# preamp_gain_stage_2.net
KiCad netlist of a schematic drawn in Altium Designer
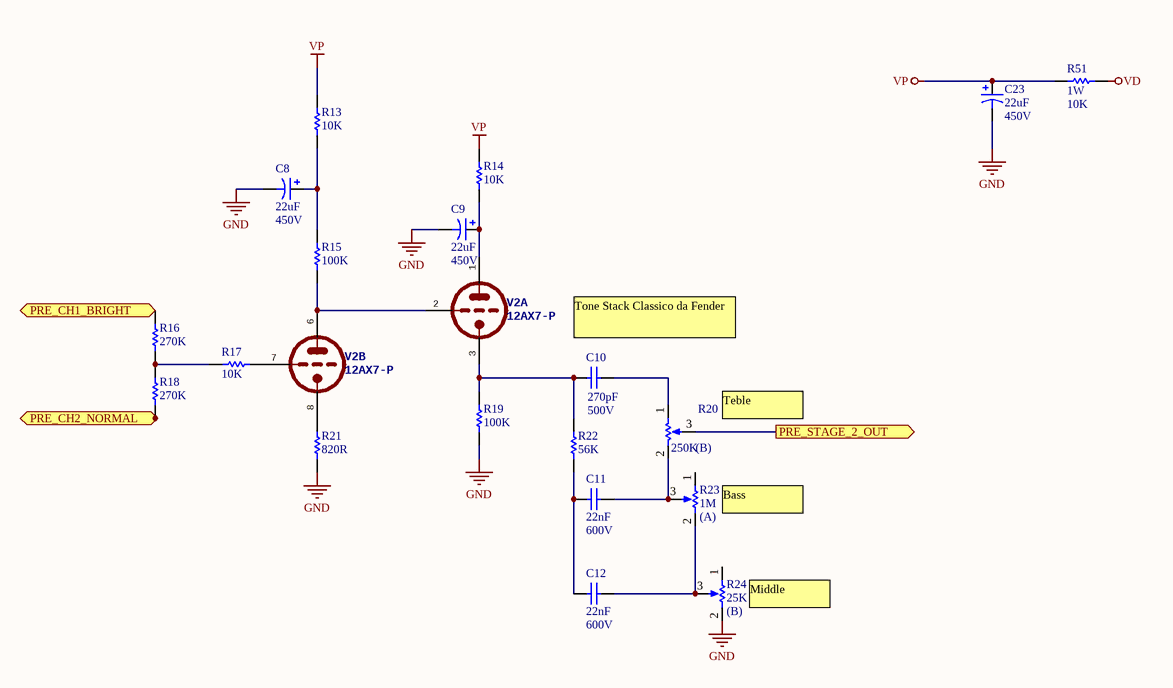
[diagram p0: preamp_gain_stage_2.SchDoc]

(export (version "E")
  (design (tool "Eeschema 10.0.6"))
  (components
    (comp (ref "C8")
      (value "22uF")
      (footprint "RAD-POL-7.6-15")
      (description "Polarized Capacitor (Axial)")
      (fields
        (field (name "VOLTAGE") "450V")
        (field (name "Comment") "Cap Pol Rad")
        (field (name "PUBLISHER") "Altium Limited")
      )
      (libsource (lib "capacitors") (part "Cap Pol Rad"))
    )
    (comp (ref "C9")
      (value "22uF")
      (footprint "RAD-POL-7.6-15")
      (description "Polarized Capacitor (Axial)")
      (fields
        (field (name "VOLTAGE") "450V")
        (field (name "Comment") "Cap Pol Rad")
        (field (name "PUBLISHER") "Altium Limited")
      )
      (libsource (lib "capacitors") (part "Cap Pol Rad"))
    )
    (comp (ref "C10")
      (value "270pF")
      (footprint "RAD-0.3")
      (description "Capacitor")
      (fields
        (field (name "VOLTAGE") "500V")
        (field (name "Comment") "Cap")
        (field (name "PUBLISHER") "Altium Limited")
      )
      (libsource (lib "Miscellaneous Devices") (part "Cap"))
    )
    (comp (ref "C11")
      (value "22nF")
      (footprint "ORANGE-DROP-22nF-600V")
      (description "Capacitor")
      (fields
        (field (name "MANUFACTURERPARTNUMBER") "715P22356KD3")
        (field (name "VOLTAGE") "600V")
        (field (name "Comment") "Orange Drop Capacitor")
        (field (name "PUBLISHER") "Linda HB Amplifiers")
      )
      (libsource (lib "capacitors") (part "Cap-Orange-DROP-22nF-600V"))
    )
    (comp (ref "C12")
      (value "22nF")
      (footprint "ORANGE-DROP-22nF-600V")
      (description "Capacitor")
      (fields
        (field (name "MANUFACTURERPARTNUMBER") "715P22356KD3")
        (field (name "VOLTAGE") "600V")
        (field (name "Comment") "Orange Drop Capacitor")
        (field (name "PUBLISHER") "Linda HB Amplifiers")
      )
      (libsource (lib "capacitors") (part "Cap-Orange-DROP-22nF-600V"))
    )
    (comp (ref "C23")
      (value "22uF")
      (footprint "RAD-POL-7.6-15")
      (description "Polarized Capacitor (Axial)")
      (fields
        (field (name "VOLTAGE") "450V")
        (field (name "Comment") "Cap Pol Rad")
        (field (name "PUBLISHER") "Altium Limited")
      )
      (libsource (lib "capacitors") (part "Cap Pol Rad"))
    )
    (comp (ref "R13")
      (value "10K")
      (footprint "AXIAL-0.6")
      (description "Semiconductor Resistor")
      (fields
        (field (name "POWER") "1/2W")
        (field (name "Comment") "Metal Film Resistor 1/2W")
        (field (name "PUBLISHER") "Whitesheep Amps")
      )
      (libsource (lib "resistors") (part "Res Metal Film 1/2W"))
    )
    (comp (ref "R14")
      (value "10K")
      (footprint "AXIAL-0.6")
      (description "Semiconductor Resistor")
      (fields
        (field (name "POWER") "1/2W")
        (field (name "Comment") "Metal Film Resistor 1/2W")
        (field (name "PUBLISHER") "Whitesheep Amps")
      )
      (libsource (lib "resistors") (part "Res Metal Film 1/2W"))
    )
    (comp (ref "R15")
      (value "100K")
      (footprint "AXIAL-0.6")
      (description "Semiconductor Resistor")
      (fields
        (field (name "POWER") "1/2W")
        (field (name "Comment") "Metal Film Resistor 1/2W")
        (field (name "PUBLISHER") "Whitesheep Amps")
      )
      (libsource (lib "resistors") (part "Res Metal Film 1/2W"))
    )
    (comp (ref "R16")
      (value "270K")
      (footprint "AXIAL-0.6")
      (description "Semiconductor Resistor")
      (fields
        (field (name "POWER") "1/2W")
        (field (name "Comment") "Metal Film Resistor 1/2W")
        (field (name "PUBLISHER") "Whitesheep Amps")
      )
      (libsource (lib "resistors") (part "Res Metal Film 1/2W"))
    )
    (comp (ref "R17")
      (value "10K")
      (footprint "AXIAL-0.6")
      (description "Semiconductor Resistor")
      (fields
        (field (name "POWER") "1/2W")
        (field (name "Comment") "Metal Film Resistor 1/2W")
        (field (name "PUBLISHER") "Whitesheep Amps")
      )
      (libsource (lib "resistors") (part "Res Metal Film 1/2W"))
    )
    (comp (ref "R18")
      (value "270K")
      (footprint "AXIAL-0.6")
      (description "Semiconductor Resistor")
      (fields
        (field (name "POWER") "1/2W")
        (field (name "Comment") "Metal Film Resistor 1/2W")
        (field (name "PUBLISHER") "Whitesheep Amps")
      )
      (libsource (lib "resistors") (part "Res Metal Film 1/2W"))
    )
    (comp (ref "R19")
      (value "100K")
      (footprint "AXIAL-0.6")
      (description "Semiconductor Resistor")
      (fields
        (field (name "POWER") "1/2W")
        (field (name "Comment") "Metal Film Resistor 1/2W")
        (field (name "PUBLISHER") "Whitesheep Amps")
      )
      (libsource (lib "resistors") (part "Res Metal Film 1/2W"))
    )
    (comp (ref "R20")
      (value "250K")
      (footprint "pot_alpha - 2.54mm")
      (description "Potentiometer")
      (fields
        (field (name "TYPE") "(B)")
        (field (name "Comment") "ALPHA Potentiometer")
        (field (name "PUBLISHER") "Altium Limited")
      )
      (libsource (lib "potentiometers") (part "alpha-pot"))
    )
    (comp (ref "R21")
      (value "820R")
      (footprint "AXIAL-0.6")
      (description "Semiconductor Resistor")
      (fields
        (field (name "POWER") "1/2W")
        (field (name "Comment") "Metal Film Resistor 1/2W")
        (field (name "PUBLISHER") "Whitesheep Amps")
      )
      (libsource (lib "resistors") (part "Res Metal Film 1/2W"))
    )
    (comp (ref "R22")
      (value "56K")
      (footprint "AXIAL-0.6")
      (description "Semiconductor Resistor")
      (fields
        (field (name "POWER") "1/2W")
        (field (name "Comment") "Metal Film Resistor 1/2W")
        (field (name "PUBLISHER") "Whitesheep Amps")
      )
      (libsource (lib "resistors") (part "Res Metal Film 1/2W"))
    )
    (comp (ref "R23")
      (value "1M")
      (footprint "pot_alpha - 2.54mm")
      (description "Potentiometer")
      (fields
        (field (name "TYPE") "(A)")
        (field (name "Comment") "ALPHA Potentiometer")
        (field (name "PUBLISHER") "Altium Limited")
      )
      (libsource (lib "potentiometers") (part "alpha-pot"))
    )
    (comp (ref "R24")
      (value "25K")
      (footprint "pot_alpha - 2.54mm")
      (description "Potentiometer")
      (fields
        (field (name "TYPE") "(B)")
        (field (name "Comment") "ALPHA Potentiometer")
        (field (name "PUBLISHER") "Altium Limited")
      )
      (libsource (lib "potentiometers") (part "alpha-pot"))
    )
    (comp (ref "R51")
      (value "10K")
      (footprint "AXIAL-0.6")
      (description "Semiconductor Resistor")
      (fields
        (field (name "POWER") "1W")
        (field (name "Comment") "Metal Film Resistor 1W")
        (field (name "PUBLISHER") "Linda Hand Buit Amplifiers")
      )
      (libsource (lib "resistors") (part "Res Wire Wound 1W"))
    )
    (comp (ref "V2")
      (value "12AX7-P")
      (footprint "NOVAL")
      (libsource (lib "eagle_tubes_v6") (part "12AX7-P"))
    )
  )
  (nets
    (net (code "1") (name "/PRE_CH1_BRIGHT") (class "Default")
      (node (ref "R16") (pin "1") (pinfunction "1_1") (pintype "passive"))
    )
    (net (code "3") (name "/PRE_STAGE_2_OUT") (class "Default")
      (node (ref "R20") (pin "3") (pinfunction "TAP_3") (pintype "passive"))
    )
    (net (code "4") (name "GND") (class "Default")
      (node (ref "C23") (pin "2") (pinfunction "2_2") (pintype "passive"))
      (node (ref "C8") (pin "2") (pinfunction "2_2") (pintype "passive"))
      (node (ref "C9") (pin "2") (pinfunction "2_2") (pintype "passive"))
      (node (ref "R19") (pin "2") (pinfunction "2_2") (pintype "passive"))
      (node (ref "R21") (pin "2") (pinfunction "2_2") (pintype "passive"))
      (node (ref "R24") (pin "2") (pinfunction "BOT_2") (pintype "passive"))
    )
    (net (code "5") (name "Net-(C8-Pad1)") (class "Default")
      (node (ref "C8") (pin "1") (pinfunction "1_1") (pintype "passive"))
      (node (ref "R13") (pin "2") (pinfunction "2_2") (pintype "passive"))
      (node (ref "R15") (pin "1") (pinfunction "1_1") (pintype "passive"))
    )
    (net (code "6") (name "Net-(C11-Pad1)") (class "Default")
      (node (ref "C11") (pin "1") (pinfunction "1_1") (pintype "passive"))
      (node (ref "C12") (pin "1") (pinfunction "1_1") (pintype "passive"))
      (node (ref "R22") (pin "2") (pinfunction "2_2") (pintype "passive"))
    )
    (net (code "7") (name "Net-(R16-Pad2)") (class "Default")
      (node (ref "R16") (pin "2") (pinfunction "2_2") (pintype "passive"))
      (node (ref "R17") (pin "1") (pinfunction "1_1") (pintype "passive"))
      (node (ref "R18") (pin "1") (pinfunction "1_1") (pintype "passive"))
    )
    (net (code "8") (name "Net-(R20-BOT)") (class "Default")
      (node (ref "C11") (pin "2") (pinfunction "2_2") (pintype "passive"))
      (node (ref "R20") (pin "2") (pinfunction "BOT_2") (pintype "passive"))
      (node (ref "R23") (pin "3") (pinfunction "TAP_3") (pintype "passive"))
    )
    (net (code "9") (name "Net-(R20-TOP)") (class "Default")
      (node (ref "C10") (pin "2") (pinfunction "2_2") (pintype "passive"))
      (node (ref "R20") (pin "1") (pinfunction "TOP_1") (pintype "passive"))
    )
    (net (code "10") (name "Net-(R23-BOT)") (class "Default")
      (node (ref "C12") (pin "2") (pinfunction "2_2") (pintype "passive"))
      (node (ref "R23") (pin "2") (pinfunction "BOT_2") (pintype "passive"))
      (node (ref "R24") (pin "3") (pinfunction "TAP_3") (pintype "passive"))
    )
    (net (code "11") (name "Net-(V2A-TA)") (class "Default")
      (node (ref "C9") (pin "1") (pinfunction "1_1") (pintype "passive"))
      (node (ref "R14") (pin "2") (pinfunction "2_2") (pintype "passive"))
      (node (ref "V2") (pin "1") (pinfunction "TA_1") (pintype "passive"))
    )
    (net (code "12") (name "Net-(V2A-TG)") (class "Default")
      (node (ref "R15") (pin "2") (pinfunction "2_2") (pintype "passive"))
      (node (ref "V2") (pin "2") (pinfunction "TG_2") (pintype "passive"))
      (node (ref "V2") (pin "6") (pinfunction "TA_6") (pintype "passive"))
    )
    (net (code "13") (name "Net-(V2A-TK)") (class "Default")
      (node (ref "C10") (pin "1") (pinfunction "1_1") (pintype "passive"))
      (node (ref "R19") (pin "1") (pinfunction "1_1") (pintype "passive"))
      (node (ref "R22") (pin "1") (pinfunction "1_1") (pintype "passive"))
      (node (ref "V2") (pin "3") (pinfunction "TK_3") (pintype "passive"))
    )
    (net (code "14") (name "Net-(V2B-TG)") (class "Default")
      (node (ref "R17") (pin "2") (pinfunction "2_2") (pintype "passive"))
      (node (ref "V2") (pin "7") (pinfunction "TG_7") (pintype "passive"))
    )
    (net (code "15") (name "Net-(V2B-TK)") (class "Default")
      (node (ref "R21") (pin "1") (pinfunction "1_1") (pintype "passive"))
      (node (ref "V2") (pin "8") (pinfunction "TK_8") (pintype "passive"))
    )
    (net (code "16") (name "VD") (class "Default")
      (node (ref "R51") (pin "2") (pinfunction "2_2") (pintype "passive"))
    )
    (net (code "17") (name "VP") (class "Default")
      (node (ref "C23") (pin "1") (pinfunction "1_1") (pintype "passive"))
      (node (ref "R13") (pin "1") (pinfunction "1_1") (pintype "passive"))
      (node (ref "R14") (pin "1") (pinfunction "1_1") (pintype "passive"))
      (node (ref "R51") (pin "1") (pinfunction "1_1") (pintype "passive"))
    )
    (net (code "18") (name "unconnected-(R18-Pad2)") (class "Default")
      (node (ref "R18") (pin "2") (pinfunction "2_2") (pintype "passive"))
    )
    (net (code "19") (name "unconnected-(R23-TOP-Pad1)") (class "Default")
      (node (ref "R23") (pin "1") (pinfunction "TOP_1") (pintype "passive"))
    )
    (net (code "20") (name "unconnected-(R24-TOP-Pad1)") (class "Default")
      (node (ref "R24") (pin "1") (pinfunction "TOP_1") (pintype "passive"))
    )
  )
)
